# dv_spectrum_row.net
KiCad netlist of a schematic drawn in Altium Designer
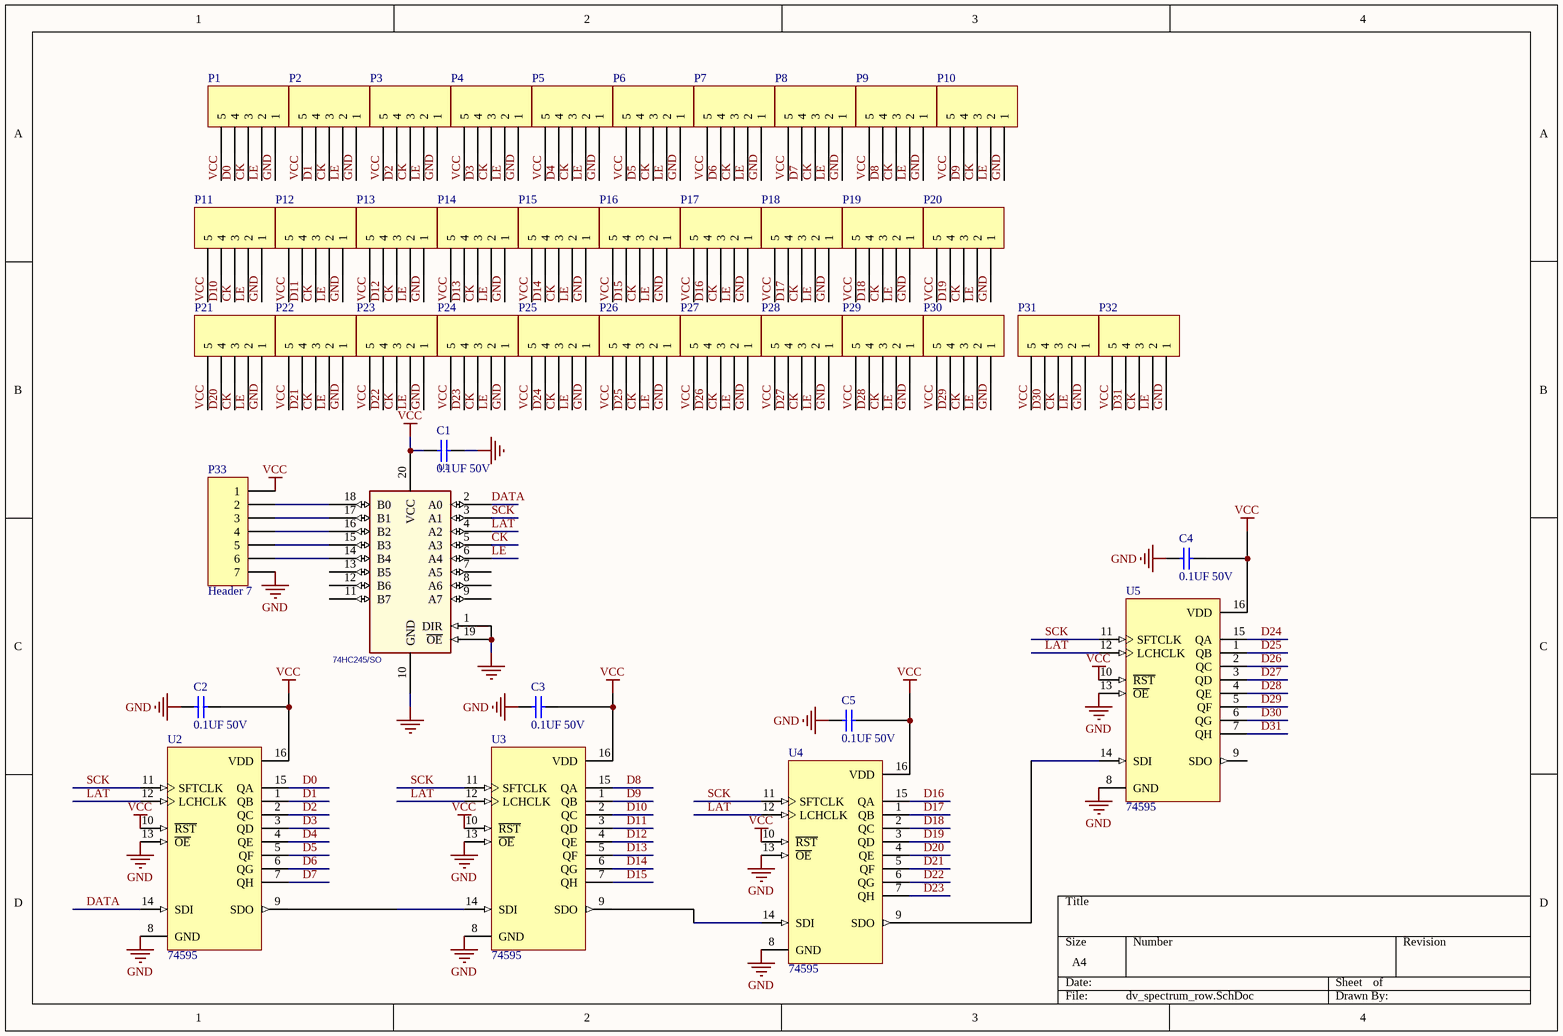
[diagram p0: dv_spectrum_row.SchDoc]

(export (version "E")
  (design (tool "Eeschema 10.0.6"))
  (components
    (comp (ref "C1")
      (value "0.1UF 50V")
      (footprint "CAPC2012X135N")
      (description "CAP CER 0.1UF 50V Y5V 0805")
      (fields
        (field (name "MANUFACTURER") "Yageo")
        (field (name "MANUFACTURER PART NUMBER") "CC0805ZRY5V9BB104")
      )
      (libsource (lib "altium-import") (part "root_1_CC0805ZRY5V9BB104_"))
    )
    (comp (ref "C2")
      (value "0.1UF 50V")
      (footprint "CAPC2012X135N")
      (description "CAP CER 0.1UF 50V Y5V 0805")
      (fields
        (field (name "MANUFACTURER") "Yageo")
        (field (name "MANUFACTURER PART NUMBER") "CC0805ZRY5V9BB104")
      )
      (libsource (lib "altium-import") (part "root_3_CC0805ZRY5V9BB104_"))
    )
    (comp (ref "C3")
      (value "0.1UF 50V")
      (footprint "CAPC2012X135N")
      (description "CAP CER 0.1UF 50V Y5V 0805")
      (fields
        (field (name "MANUFACTURER") "Yageo")
        (field (name "MANUFACTURER PART NUMBER") "CC0805ZRY5V9BB104")
      )
      (libsource (lib "altium-import") (part "root_1_CC0805ZRY5V9BB104_"))
    )
    (comp (ref "C4")
      (value "0.1UF 50V")
      (footprint "CAPC2012X135N")
      (description "CAP CER 0.1UF 50V Y5V 0805")
      (fields
        (field (name "MANUFACTURER") "Yageo")
        (field (name "MANUFACTURER PART NUMBER") "CC0805ZRY5V9BB104")
      )
      (libsource (lib "altium-import") (part "root_1_CC0805ZRY5V9BB104_"))
    )
    (comp (ref "C5")
      (value "0.1UF 50V")
      (footprint "CAPC2012X135N")
      (description "CAP CER 0.1UF 50V Y5V 0805")
      (fields
        (field (name "MANUFACTURER") "Yageo")
        (field (name "MANUFACTURER PART NUMBER") "CC0805ZRY5V9BB104")
      )
      (libsource (lib "altium-import") (part "root_1_CC0805ZRY5V9BB104_"))
    )
    (comp (ref "P1")
      (value "Header 5")
      (footprint "HDR1X5")
      (description "Header, 5-Pin")
      (fields (field (name "PUBLISHER") "Altium Limited"))
      (libsource (lib "Miscellaneous Connectors") (part "Header 5"))
    )
    (comp (ref "P2")
      (value "Header 5")
      (footprint "HDR1X5")
      (description "Header, 5-Pin")
      (fields (field (name "PUBLISHER") "Altium Limited"))
      (libsource (lib "Miscellaneous Connectors") (part "Header 5"))
    )
    (comp (ref "P3")
      (value "Header 5")
      (footprint "HDR1X5")
      (description "Header, 5-Pin")
      (fields (field (name "PUBLISHER") "Altium Limited"))
      (libsource (lib "Miscellaneous Connectors") (part "Header 5"))
    )
    (comp (ref "P4")
      (value "Header 5")
      (footprint "HDR1X5")
      (description "Header, 5-Pin")
      (fields (field (name "PUBLISHER") "Altium Limited"))
      (libsource (lib "Miscellaneous Connectors") (part "Header 5"))
    )
    (comp (ref "P5")
      (value "Header 5")
      (footprint "HDR1X5")
      (description "Header, 5-Pin")
      (fields (field (name "PUBLISHER") "Altium Limited"))
      (libsource (lib "Miscellaneous Connectors") (part "Header 5"))
    )
    (comp (ref "P6")
      (value "Header 5")
      (footprint "HDR1X5")
      (description "Header, 5-Pin")
      (fields (field (name "PUBLISHER") "Altium Limited"))
      (libsource (lib "Miscellaneous Connectors") (part "Header 5"))
    )
    (comp (ref "P7")
      (value "Header 5")
      (footprint "HDR1X5")
      (description "Header, 5-Pin")
      (fields (field (name "PUBLISHER") "Altium Limited"))
      (libsource (lib "Miscellaneous Connectors") (part "Header 5"))
    )
    (comp (ref "P8")
      (value "Header 5")
      (footprint "HDR1X5")
      (description "Header, 5-Pin")
      (fields (field (name "PUBLISHER") "Altium Limited"))
      (libsource (lib "Miscellaneous Connectors") (part "Header 5"))
    )
    (comp (ref "P9")
      (value "Header 5")
      (footprint "HDR1X5")
      (description "Header, 5-Pin")
      (fields (field (name "PUBLISHER") "Altium Limited"))
      (libsource (lib "Miscellaneous Connectors") (part "Header 5"))
    )
    (comp (ref "P10")
      (value "Header 5")
      (footprint "HDR1X5")
      (description "Header, 5-Pin")
      (fields (field (name "PUBLISHER") "Altium Limited"))
      (libsource (lib "Miscellaneous Connectors") (part "Header 5"))
    )
    (comp (ref "P11")
      (value "Header 5")
      (footprint "HDR1X5")
      (description "Header, 5-Pin")
      (fields (field (name "PUBLISHER") "Altium Limited"))
      (libsource (lib "Miscellaneous Connectors") (part "Header 5"))
    )
    (comp (ref "P12")
      (value "Header 5")
      (footprint "HDR1X5")
      (description "Header, 5-Pin")
      (fields (field (name "PUBLISHER") "Altium Limited"))
      (libsource (lib "Miscellaneous Connectors") (part "Header 5"))
    )
    (comp (ref "P13")
      (value "Header 5")
      (footprint "HDR1X5")
      (description "Header, 5-Pin")
      (fields (field (name "PUBLISHER") "Altium Limited"))
      (libsource (lib "Miscellaneous Connectors") (part "Header 5"))
    )
    (comp (ref "P14")
      (value "Header 5")
      (footprint "HDR1X5")
      (description "Header, 5-Pin")
      (fields (field (name "PUBLISHER") "Altium Limited"))
      (libsource (lib "Miscellaneous Connectors") (part "Header 5"))
    )
    (comp (ref "P15")
      (value "Header 5")
      (footprint "HDR1X5")
      (description "Header, 5-Pin")
      (fields (field (name "PUBLISHER") "Altium Limited"))
      (libsource (lib "Miscellaneous Connectors") (part "Header 5"))
    )
    (comp (ref "P16")
      (value "Header 5")
      (footprint "HDR1X5")
      (description "Header, 5-Pin")
      (fields (field (name "PUBLISHER") "Altium Limited"))
      (libsource (lib "Miscellaneous Connectors") (part "Header 5"))
    )
    (comp (ref "P17")
      (value "Header 5")
      (footprint "HDR1X5")
      (description "Header, 5-Pin")
      (fields (field (name "PUBLISHER") "Altium Limited"))
      (libsource (lib "Miscellaneous Connectors") (part "Header 5"))
    )
    (comp (ref "P18")
      (value "Header 5")
      (footprint "HDR1X5")
      (description "Header, 5-Pin")
      (fields (field (name "PUBLISHER") "Altium Limited"))
      (libsource (lib "Miscellaneous Connectors") (part "Header 5"))
    )
    (comp (ref "P19")
      (value "Header 5")
      (footprint "HDR1X5")
      (description "Header, 5-Pin")
      (fields (field (name "PUBLISHER") "Altium Limited"))
      (libsource (lib "Miscellaneous Connectors") (part "Header 5"))
    )
    (comp (ref "P20")
      (value "Header 5")
      (footprint "HDR1X5")
      (description "Header, 5-Pin")
      (fields (field (name "PUBLISHER") "Altium Limited"))
      (libsource (lib "Miscellaneous Connectors") (part "Header 5"))
    )
    (comp (ref "P21")
      (value "Header 5")
      (footprint "HDR1X5")
      (description "Header, 5-Pin")
      (fields (field (name "PUBLISHER") "Altium Limited"))
      (libsource (lib "Miscellaneous Connectors") (part "Header 5"))
    )
    (comp (ref "P22")
      (value "Header 5")
      (footprint "HDR1X5")
      (description "Header, 5-Pin")
      (fields (field (name "PUBLISHER") "Altium Limited"))
      (libsource (lib "Miscellaneous Connectors") (part "Header 5"))
    )
    (comp (ref "P23")
      (value "Header 5")
      (footprint "HDR1X5")
      (description "Header, 5-Pin")
      (fields (field (name "PUBLISHER") "Altium Limited"))
      (libsource (lib "Miscellaneous Connectors") (part "Header 5"))
    )
    (comp (ref "P24")
      (value "Header 5")
      (footprint "HDR1X5")
      (description "Header, 5-Pin")
      (fields (field (name "PUBLISHER") "Altium Limited"))
      (libsource (lib "Miscellaneous Connectors") (part "Header 5"))
    )
    (comp (ref "P25")
      (value "Header 5")
      (footprint "HDR1X5")
      (description "Header, 5-Pin")
      (fields (field (name "PUBLISHER") "Altium Limited"))
      (libsource (lib "Miscellaneous Connectors") (part "Header 5"))
    )
    (comp (ref "P26")
      (value "Header 5")
      (footprint "HDR1X5")
      (description "Header, 5-Pin")
      (fields (field (name "PUBLISHER") "Altium Limited"))
      (libsource (lib "Miscellaneous Connectors") (part "Header 5"))
    )
    (comp (ref "P27")
      (value "Header 5")
      (footprint "HDR1X5")
      (description "Header, 5-Pin")
      (fields (field (name "PUBLISHER") "Altium Limited"))
      (libsource (lib "Miscellaneous Connectors") (part "Header 5"))
    )
    (comp (ref "P28")
      (value "Header 5")
      (footprint "HDR1X5")
      (description "Header, 5-Pin")
      (fields (field (name "PUBLISHER") "Altium Limited"))
      (libsource (lib "Miscellaneous Connectors") (part "Header 5"))
    )
    (comp (ref "P29")
      (value "Header 5")
      (footprint "HDR1X5")
      (description "Header, 5-Pin")
      (fields (field (name "PUBLISHER") "Altium Limited"))
      (libsource (lib "Miscellaneous Connectors") (part "Header 5"))
    )
    (comp (ref "P30")
      (value "Header 5")
      (footprint "HDR1X5")
      (description "Header, 5-Pin")
      (fields (field (name "PUBLISHER") "Altium Limited"))
      (libsource (lib "Miscellaneous Connectors") (part "Header 5"))
    )
    (comp (ref "P31")
      (value "Header 5")
      (footprint "HDR1X5")
      (description "Header, 5-Pin")
      (fields (field (name "PUBLISHER") "Altium Limited"))
      (libsource (lib "Miscellaneous Connectors") (part "Header 5"))
    )
    (comp (ref "P32")
      (value "Header 5")
      (footprint "HDR1X5")
      (description "Header, 5-Pin")
      (fields (field (name "PUBLISHER") "Altium Limited"))
      (libsource (lib "Miscellaneous Connectors") (part "Header 5"))
    )
    (comp (ref "P33")
      (value "Header 7")
      (footprint "HDR1X7")
      (description "Header, 7-Pin")
      (fields (field (name "PUBLISHER") "Altium Limited"))
      (libsource (lib "Miscellaneous Connectors") (part "Header 7"))
    )
    (comp (ref "U1") (value "74HC245/SO") (libsource (lib "*") (part "74HC245/SO_1")))
    (comp (ref "U2")
      (value "74595")
      (footprint "SO16-150mil")
      (description "8-Bit Serial-Input/Serial or Prallel-Output Shift Register with Latched 3-State Outputs")
      (fields (field (name "PUBLISHER") "Altium Limited"))
      (libsource (lib "General IC") (part "74595"))
    )
    (comp (ref "U3")
      (value "74595")
      (footprint "SO16-150mil")
      (description "8-Bit Serial-Input/Serial or Prallel-Output Shift Register with Latched 3-State Outputs")
      (fields (field (name "PUBLISHER") "Altium Limited"))
      (libsource (lib "General IC") (part "74595"))
    )
    (comp (ref "U4")
      (value "74595")
      (footprint "SO16-150mil")
      (description "8-Bit Serial-Input/Serial or Prallel-Output Shift Register with Latched 3-State Outputs")
      (fields (field (name "PUBLISHER") "Altium Limited"))
      (libsource (lib "General IC") (part "74595"))
    )
    (comp (ref "U5")
      (value "74595")
      (footprint "SO16-150mil")
      (description "8-Bit Serial-Input/Serial or Prallel-Output Shift Register with Latched 3-State Outputs")
      (fields (field (name "PUBLISHER") "Altium Limited"))
      (libsource (lib "General IC") (part "74595"))
    )
  )
  (nets
    (net (code "1") (name "/CK") (class "Default")
      (node (ref "P1") (pin "3") (pinfunction "3_3") (pintype "passive"))
      (node (ref "P10") (pin "3") (pinfunction "3_3") (pintype "passive"))
      (node (ref "P11") (pin "3") (pinfunction "3_3") (pintype "passive"))
      (node (ref "P12") (pin "3") (pinfunction "3_3") (pintype "passive"))
      (node (ref "P13") (pin "3") (pinfunction "3_3") (pintype "passive"))
      (node (ref "P14") (pin "3") (pinfunction "3_3") (pintype "passive"))
      (node (ref "P15") (pin "3") (pinfunction "3_3") (pintype "passive"))
      (node (ref "P16") (pin "3") (pinfunction "3_3") (pintype "passive"))
      (node (ref "P17") (pin "3") (pinfunction "3_3") (pintype "passive"))
      (node (ref "P18") (pin "3") (pinfunction "3_3") (pintype "passive"))
      (node (ref "P19") (pin "3") (pinfunction "3_3") (pintype "passive"))
      (node (ref "P2") (pin "3") (pinfunction "3_3") (pintype "passive"))
      (node (ref "P20") (pin "3") (pinfunction "3_3") (pintype "passive"))
      (node (ref "P21") (pin "3") (pinfunction "3_3") (pintype "passive"))
      (node (ref "P22") (pin "3") (pinfunction "3_3") (pintype "passive"))
      (node (ref "P23") (pin "3") (pinfunction "3_3") (pintype "passive"))
      (node (ref "P24") (pin "3") (pinfunction "3_3") (pintype "passive"))
      (node (ref "P25") (pin "3") (pinfunction "3_3") (pintype "passive"))
      (node (ref "P26") (pin "3") (pinfunction "3_3") (pintype "passive"))
      (node (ref "P27") (pin "3") (pinfunction "3_3") (pintype "passive"))
      (node (ref "P28") (pin "3") (pinfunction "3_3") (pintype "passive"))
      (node (ref "P29") (pin "3") (pinfunction "3_3") (pintype "passive"))
      (node (ref "P3") (pin "3") (pinfunction "3_3") (pintype "passive"))
      (node (ref "P30") (pin "3") (pinfunction "3_3") (pintype "passive"))
      (node (ref "P31") (pin "3") (pinfunction "3_3") (pintype "passive"))
      (node (ref "P32") (pin "3") (pinfunction "3_3") (pintype "passive"))
      (node (ref "P4") (pin "3") (pinfunction "3_3") (pintype "passive"))
      (node (ref "P5") (pin "3") (pinfunction "3_3") (pintype "passive"))
      (node (ref "P6") (pin "3") (pinfunction "3_3") (pintype "passive"))
      (node (ref "P7") (pin "3") (pinfunction "3_3") (pintype "passive"))
      (node (ref "P8") (pin "3") (pinfunction "3_3") (pintype "passive"))
      (node (ref "P9") (pin "3") (pinfunction "3_3") (pintype "passive"))
      (node (ref "U1") (pin "5") (pinfunction "A3_5") (pintype "bidirectional"))
    )
    (net (code "2") (name "/D0") (class "Default")
      (node (ref "P1") (pin "4") (pinfunction "4_4") (pintype "passive"))
      (node (ref "U2") (pin "15") (pinfunction "QA_15") (pintype "tri_state"))
    )
    (net (code "3") (name "/D1") (class "Default")
      (node (ref "P2") (pin "4") (pinfunction "4_4") (pintype "passive"))
      (node (ref "U2") (pin "1") (pinfunction "QB_1") (pintype "tri_state"))
    )
    (net (code "4") (name "/D2") (class "Default")
      (node (ref "P3") (pin "4") (pinfunction "4_4") (pintype "passive"))
      (node (ref "U2") (pin "2") (pinfunction "QC_2") (pintype "tri_state"))
    )
    (net (code "5") (name "/D3") (class "Default")
      (node (ref "P4") (pin "4") (pinfunction "4_4") (pintype "passive"))
      (node (ref "U2") (pin "3") (pinfunction "QD_3") (pintype "tri_state"))
    )
    (net (code "6") (name "/D4") (class "Default")
      (node (ref "P5") (pin "4") (pinfunction "4_4") (pintype "passive"))
      (node (ref "U2") (pin "4") (pinfunction "QE_4") (pintype "tri_state"))
    )
    (net (code "7") (name "/D5") (class "Default")
      (node (ref "P6") (pin "4") (pinfunction "4_4") (pintype "passive"))
      (node (ref "U2") (pin "5") (pinfunction "QF_5") (pintype "tri_state"))
    )
    (net (code "8") (name "/D6") (class "Default")
      (node (ref "P7") (pin "4") (pinfunction "4_4") (pintype "passive"))
      (node (ref "U2") (pin "6") (pinfunction "QG_6") (pintype "tri_state"))
    )
    (net (code "9") (name "/D7") (class "Default")
      (node (ref "P8") (pin "4") (pinfunction "4_4") (pintype "passive"))
      (node (ref "U2") (pin "7") (pinfunction "QH_7") (pintype "tri_state"))
    )
    (net (code "10") (name "/D8") (class "Default")
      (node (ref "P9") (pin "4") (pinfunction "4_4") (pintype "passive"))
      (node (ref "U3") (pin "15") (pinfunction "QA_15") (pintype "tri_state"))
    )
    (net (code "11") (name "/D9") (class "Default")
      (node (ref "P10") (pin "4") (pinfunction "4_4") (pintype "passive"))
      (node (ref "U3") (pin "1") (pinfunction "QB_1") (pintype "tri_state"))
    )
    (net (code "12") (name "/D10") (class "Default")
      (node (ref "P11") (pin "4") (pinfunction "4_4") (pintype "passive"))
      (node (ref "U3") (pin "2") (pinfunction "QC_2") (pintype "tri_state"))
    )
    (net (code "13") (name "/D11") (class "Default")
      (node (ref "P12") (pin "4") (pinfunction "4_4") (pintype "passive"))
      (node (ref "U3") (pin "3") (pinfunction "QD_3") (pintype "tri_state"))
    )
    (net (code "14") (name "/D12") (class "Default")
      (node (ref "P13") (pin "4") (pinfunction "4_4") (pintype "passive"))
      (node (ref "U3") (pin "4") (pinfunction "QE_4") (pintype "tri_state"))
    )
    (net (code "15") (name "/D13") (class "Default")
      (node (ref "P14") (pin "4") (pinfunction "4_4") (pintype "passive"))
      (node (ref "U3") (pin "5") (pinfunction "QF_5") (pintype "tri_state"))
    )
    (net (code "16") (name "/D14") (class "Default")
      (node (ref "P15") (pin "4") (pinfunction "4_4") (pintype "passive"))
      (node (ref "U3") (pin "6") (pinfunction "QG_6") (pintype "tri_state"))
    )
    (net (code "17") (name "/D15") (class "Default")
      (node (ref "P16") (pin "4") (pinfunction "4_4") (pintype "passive"))
      (node (ref "U3") (pin "7") (pinfunction "QH_7") (pintype "tri_state"))
    )
    (net (code "18") (name "/D16") (class "Default")
      (node (ref "P17") (pin "4") (pinfunction "4_4") (pintype "passive"))
      (node (ref "U4") (pin "15") (pinfunction "QA_15") (pintype "tri_state"))
    )
    (net (code "19") (name "/D17") (class "Default")
      (node (ref "P18") (pin "4") (pinfunction "4_4") (pintype "passive"))
      (node (ref "U4") (pin "1") (pinfunction "QB_1") (pintype "tri_state"))
    )
    (net (code "20") (name "/D18") (class "Default")
      (node (ref "P19") (pin "4") (pinfunction "4_4") (pintype "passive"))
      (node (ref "U4") (pin "2") (pinfunction "QC_2") (pintype "tri_state"))
    )
    (net (code "21") (name "/D19") (class "Default")
      (node (ref "P20") (pin "4") (pinfunction "4_4") (pintype "passive"))
      (node (ref "U4") (pin "3") (pinfunction "QD_3") (pintype "tri_state"))
    )
    (net (code "22") (name "/D20") (class "Default")
      (node (ref "P21") (pin "4") (pinfunction "4_4") (pintype "passive"))
      (node (ref "U4") (pin "4") (pinfunction "QE_4") (pintype "tri_state"))
    )
    (net (code "23") (name "/D21") (class "Default")
      (node (ref "P22") (pin "4") (pinfunction "4_4") (pintype "passive"))
      (node (ref "U4") (pin "5") (pinfunction "QF_5") (pintype "tri_state"))
    )
    (net (code "24") (name "/D22") (class "Default")
      (node (ref "P23") (pin "4") (pinfunction "4_4") (pintype "passive"))
      (node (ref "U4") (pin "6") (pinfunction "QG_6") (pintype "tri_state"))
    )
    (net (code "25") (name "/D23") (class "Default")
      (node (ref "P24") (pin "4") (pinfunction "4_4") (pintype "passive"))
      (node (ref "U4") (pin "7") (pinfunction "QH_7") (pintype "tri_state"))
    )
    (net (code "26") (name "/D24") (class "Default")
      (node (ref "P25") (pin "4") (pinfunction "4_4") (pintype "passive"))
      (node (ref "U5") (pin "15") (pinfunction "QA_15") (pintype "tri_state"))
    )
    (net (code "27") (name "/D25") (class "Default")
      (node (ref "P26") (pin "4") (pinfunction "4_4") (pintype "passive"))
      (node (ref "U5") (pin "1") (pinfunction "QB_1") (pintype "tri_state"))
    )
    (net (code "28") (name "/D26") (class "Default")
      (node (ref "P27") (pin "4") (pinfunction "4_4") (pintype "passive"))
      (node (ref "U5") (pin "2") (pinfunction "QC_2") (pintype "tri_state"))
    )
    (net (code "29") (name "/D27") (class "Default")
      (node (ref "P28") (pin "4") (pinfunction "4_4") (pintype "passive"))
      (node (ref "U5") (pin "3") (pinfunction "QD_3") (pintype "tri_state"))
    )
    (net (code "30") (name "/D28") (class "Default")
      (node (ref "P29") (pin "4") (pinfunction "4_4") (pintype "passive"))
      (node (ref "U5") (pin "4") (pinfunction "QE_4") (pintype "tri_state"))
    )
    (net (code "31") (name "/D29") (class "Default")
      (node (ref "P30") (pin "4") (pinfunction "4_4") (pintype "passive"))
      (node (ref "U5") (pin "5") (pinfunction "QF_5") (pintype "tri_state"))
    )
    (net (code "32") (name "/D30") (class "Default")
      (node (ref "P31") (pin "4") (pinfunction "4_4") (pintype "passive"))
      (node (ref "U5") (pin "6") (pinfunction "QG_6") (pintype "tri_state"))
    )
    (net (code "33") (name "/D31") (class "Default")
      (node (ref "P32") (pin "4") (pinfunction "4_4") (pintype "passive"))
      (node (ref "U5") (pin "7") (pinfunction "QH_7") (pintype "tri_state"))
    )
    (net (code "34") (name "/DATA") (class "Default")
      (node (ref "U1") (pin "2") (pinfunction "A0_2") (pintype "bidirectional"))
      (node (ref "U2") (pin "14") (pinfunction "SDI_14") (pintype "input"))
    )
    (net (code "35") (name "/LAT") (class "Default")
      (node (ref "U1") (pin "4") (pinfunction "A2_4") (pintype "bidirectional"))
      (node (ref "U2") (pin "12") (pinfunction "LCHCLK_12") (pintype "input"))
      (node (ref "U3") (pin "12") (pinfunction "LCHCLK_12") (pintype "input"))
      (node (ref "U4") (pin "12") (pinfunction "LCHCLK_12") (pintype "input"))
      (node (ref "U5") (pin "12") (pinfunction "LCHCLK_12") (pintype "input"))
    )
    (net (code "36") (name "/LE") (class "Default")
      (node (ref "P1") (pin "2") (pinfunction "2_2") (pintype "passive"))
      (node (ref "P10") (pin "2") (pinfunction "2_2") (pintype "passive"))
      (node (ref "P11") (pin "2") (pinfunction "2_2") (pintype "passive"))
      (node (ref "P12") (pin "2") (pinfunction "2_2") (pintype "passive"))
      (node (ref "P13") (pin "2") (pinfunction "2_2") (pintype "passive"))
      (node (ref "P14") (pin "2") (pinfunction "2_2") (pintype "passive"))
      (node (ref "P15") (pin "2") (pinfunction "2_2") (pintype "passive"))
      (node (ref "P16") (pin "2") (pinfunction "2_2") (pintype "passive"))
      (node (ref "P17") (pin "2") (pinfunction "2_2") (pintype "passive"))
      (node (ref "P18") (pin "2") (pinfunction "2_2") (pintype "passive"))
      (node (ref "P19") (pin "2") (pinfunction "2_2") (pintype "passive"))
      (node (ref "P2") (pin "2") (pinfunction "2_2") (pintype "passive"))
      (node (ref "P20") (pin "2") (pinfunction "2_2") (pintype "passive"))
      (node (ref "P21") (pin "2") (pinfunction "2_2") (pintype "passive"))
      (node (ref "P22") (pin "2") (pinfunction "2_2") (pintype "passive"))
      (node (ref "P23") (pin "2") (pinfunction "2_2") (pintype "passive"))
      (node (ref "P24") (pin "2") (pinfunction "2_2") (pintype "passive"))
      (node (ref "P25") (pin "2") (pinfunction "2_2") (pintype "passive"))
      (node (ref "P26") (pin "2") (pinfunction "2_2") (pintype "passive"))
      (node (ref "P27") (pin "2") (pinfunction "2_2") (pintype "passive"))
      (node (ref "P28") (pin "2") (pinfunction "2_2") (pintype "passive"))
      (node (ref "P29") (pin "2") (pinfunction "2_2") (pintype "passive"))
      (node (ref "P3") (pin "2") (pinfunction "2_2") (pintype "passive"))
      (node (ref "P30") (pin "2") (pinfunction "2_2") (pintype "passive"))
      (node (ref "P31") (pin "2") (pinfunction "2_2") (pintype "passive"))
      (node (ref "P32") (pin "2") (pinfunction "2_2") (pintype "passive"))
      (node (ref "P4") (pin "2") (pinfunction "2_2") (pintype "passive"))
      (node (ref "P5") (pin "2") (pinfunction "2_2") (pintype "passive"))
      (node (ref "P6") (pin "2") (pinfunction "2_2") (pintype "passive"))
      (node (ref "P7") (pin "2") (pinfunction "2_2") (pintype "passive"))
      (node (ref "P8") (pin "2") (pinfunction "2_2") (pintype "passive"))
      (node (ref "P9") (pin "2") (pinfunction "2_2") (pintype "passive"))
      (node (ref "U1") (pin "6") (pinfunction "A4_6") (pintype "bidirectional"))
    )
    (net (code "37") (name "/SCK") (class "Default")
      (node (ref "U1") (pin "3") (pinfunction "A1_3") (pintype "bidirectional"))
      (node (ref "U2") (pin "11") (pinfunction "SFTCLK_11") (pintype "input"))
      (node (ref "U3") (pin "11") (pinfunction "SFTCLK_11") (pintype "input"))
      (node (ref "U4") (pin "11") (pinfunction "SFTCLK_11") (pintype "input"))
      (node (ref "U5") (pin "11") (pinfunction "SFTCLK_11") (pintype "input"))
    )
    (net (code "38") (name "GND") (class "Default")
      (node (ref "C1") (pin "1") (pinfunction "1_1") (pintype "passive"))
      (node (ref "C2") (pin "1") (pinfunction "1_1") (pintype "passive"))
      (node (ref "C3") (pin "2") (pinfunction "2_2") (pintype "passive"))
      (node (ref "C4") (pin "2") (pinfunction "2_2") (pintype "passive"))
      (node (ref "C5") (pin "2") (pinfunction "2_2") (pintype "passive"))
      (node (ref "P1") (pin "1") (pinfunction "1_1") (pintype "passive"))
      (node (ref "P10") (pin "1") (pinfunction "1_1") (pintype "passive"))
      (node (ref "P11") (pin "1") (pinfunction "1_1") (pintype "passive"))
      (node (ref "P12") (pin "1") (pinfunction "1_1") (pintype "passive"))
      (node (ref "P13") (pin "1") (pinfunction "1_1") (pintype "passive"))
      (node (ref "P14") (pin "1") (pinfunction "1_1") (pintype "passive"))
      (node (ref "P15") (pin "1") (pinfunction "1_1") (pintype "passive"))
      (node (ref "P16") (pin "1") (pinfunction "1_1") (pintype "passive"))
      (node (ref "P17") (pin "1") (pinfunction "1_1") (pintype "passive"))
      (node (ref "P18") (pin "1") (pinfunction "1_1") (pintype "passive"))
      (node (ref "P19") (pin "1") (pinfunction "1_1") (pintype "passive"))
      (node (ref "P2") (pin "1") (pinfunction "1_1") (pintype "passive"))
      (node (ref "P20") (pin "1") (pinfunction "1_1") (pintype "passive"))
      (node (ref "P21") (pin "1") (pinfunction "1_1") (pintype "passive"))
      (node (ref "P22") (pin "1") (pinfunction "1_1") (pintype "passive"))
      (node (ref "P23") (pin "1") (pinfunction "1_1") (pintype "passive"))
      (node (ref "P24") (pin "1") (pinfunction "1_1") (pintype "passive"))
      (node (ref "P25") (pin "1") (pinfunction "1_1") (pintype "passive"))
      (node (ref "P26") (pin "1") (pinfunction "1_1") (pintype "passive"))
      (node (ref "P27") (pin "1") (pinfunction "1_1") (pintype "passive"))
      (node (ref "P28") (pin "1") (pinfunction "1_1") (pintype "passive"))
      (node (ref "P29") (pin "1") (pinfunction "1_1") (pintype "passive"))
      (node (ref "P3") (pin "1") (pinfunction "1_1") (pintype "passive"))
      (node (ref "P30") (pin "1") (pinfunction "1_1") (pintype "passive"))
      (node (ref "P31") (pin "1") (pinfunction "1_1") (pintype "passive"))
      (node (ref "P32") (pin "1") (pinfunction "1_1") (pintype "passive"))
      (node (ref "P33") (pin "7") (pinfunction "7_7") (pintype "passive"))
      (node (ref "P4") (pin "1") (pinfunction "1_1") (pintype "passive"))
      (node (ref "P5") (pin "1") (pinfunction "1_1") (pintype "passive"))
      (node (ref "P6") (pin "1") (pinfunction "1_1") (pintype "passive"))
      (node (ref "P7") (pin "1") (pinfunction "1_1") (pintype "passive"))
      (node (ref "P8") (pin "1") (pinfunction "1_1") (pintype "passive"))
      (node (ref "P9") (pin "1") (pinfunction "1_1") (pintype "passive"))
      (node (ref "U1") (pin "1") (pinfunction "DIR_1") (pintype "input"))
      (node (ref "U1") (pin "10") (pinfunction "GND_10") (pintype "power_in"))
      (node (ref "U1") (pin "19") (pinfunction "~{OE}_19") (pintype "input"))
      (node (ref "U2") (pin "13") (pinfunction "~{OE}_13") (pintype "input"))
      (node (ref "U2") (pin "8") (pinfunction "GND_8") (pintype "power_in"))
      (node (ref "U3") (pin "13") (pinfunction "~{OE}_13") (pintype "input"))
      (node (ref "U3") (pin "8") (pinfunction "GND_8") (pintype "power_in"))
      (node (ref "U4") (pin "13") (pinfunction "~{OE}_13") (pintype "input"))
      (node (ref "U4") (pin "8") (pinfunction "GND_8") (pintype "power_in"))
      (node (ref "U5") (pin "13") (pinfunction "~{OE}_13") (pintype "input"))
      (node (ref "U5") (pin "8") (pinfunction "GND_8") (pintype "power_in"))
    )
    (net (code "39") (name "Net-(U1-B0)") (class "Default")
      (node (ref "P33") (pin "2") (pinfunction "2_2") (pintype "passive"))
      (node (ref "U1") (pin "18") (pinfunction "B0_18") (pintype "bidirectional"))
    )
    (net (code "40") (name "Net-(U1-B1)") (class "Default")
      (node (ref "P33") (pin "3") (pinfunction "3_3") (pintype "passive"))
      (node (ref "U1") (pin "17") (pinfunction "B1_17") (pintype "bidirectional"))
    )
    (net (code "41") (name "Net-(U1-B2)") (class "Default")
      (node (ref "P33") (pin "4") (pinfunction "4_4") (pintype "passive"))
      (node (ref "U1") (pin "16") (pinfunction "B2_16") (pintype "bidirectional"))
    )
    (net (code "42") (name "Net-(U1-B3)") (class "Default")
      (node (ref "P33") (pin "5") (pinfunction "5_5") (pintype "passive"))
      (node (ref "U1") (pin "15") (pinfunction "B3_15") (pintype "bidirectional"))
    )
    (net (code "43") (name "Net-(U1-B4)") (class "Default")
      (node (ref "P33") (pin "6") (pinfunction "6_6") (pintype "passive"))
      (node (ref "U1") (pin "14") (pinfunction "B4_14") (pintype "bidirectional"))
    )
    (net (code "44") (name "Net-(U2-SDO)") (class "Default")
      (node (ref "U2") (pin "9") (pinfunction "SDO_9") (pintype "output"))
      (node (ref "U3") (pin "14") (pinfunction "SDI_14") (pintype "input"))
    )
    (net (code "45") (name "Net-(U3-SDO)") (class "Default")
      (node (ref "U3") (pin "9") (pinfunction "SDO_9") (pintype "output"))
      (node (ref "U4") (pin "14") (pinfunction "SDI_14") (pintype "input"))
    )
    (net (code "46") (name "Net-(U4-SDO)") (class "Default")
      (node (ref "U4") (pin "9") (pinfunction "SDO_9") (pintype "output"))
      (node (ref "U5") (pin "14") (pinfunction "SDI_14") (pintype "input"))
    )
    (net (code "47") (name "VCC") (class "Default")
      (node (ref "C1") (pin "2") (pinfunction "2_2") (pintype "passive"))
      (node (ref "C2") (pin "2") (pinfunction "2_2") (pintype "passive"))
      (node (ref "C3") (pin "1") (pinfunction "1_1") (pintype "passive"))
      (node (ref "C4") (pin "1") (pinfunction "1_1") (pintype "passive"))
      (node (ref "C5") (pin "1") (pinfunction "1_1") (pintype "passive"))
      (node (ref "P1") (pin "5") (pinfunction "5_5") (pintype "passive"))
      (node (ref "P10") (pin "5") (pinfunction "5_5") (pintype "passive"))
      (node (ref "P11") (pin "5") (pinfunction "5_5") (pintype "passive"))
      (node (ref "P12") (pin "5") (pinfunction "5_5") (pintype "passive"))
      (node (ref "P13") (pin "5") (pinfunction "5_5") (pintype "passive"))
      (node (ref "P14") (pin "5") (pinfunction "5_5") (pintype "passive"))
      (node (ref "P15") (pin "5") (pinfunction "5_5") (pintype "passive"))
      (node (ref "P16") (pin "5") (pinfunction "5_5") (pintype "passive"))
      (node (ref "P17") (pin "5") (pinfunction "5_5") (pintype "passive"))
      (node (ref "P18") (pin "5") (pinfunction "5_5") (pintype "passive"))
      (node (ref "P19") (pin "5") (pinfunction "5_5") (pintype "passive"))
      (node (ref "P2") (pin "5") (pinfunction "5_5") (pintype "passive"))
      (node (ref "P20") (pin "5") (pinfunction "5_5") (pintype "passive"))
      (node (ref "P21") (pin "5") (pinfunction "5_5") (pintype "passive"))
      (node (ref "P22") (pin "5") (pinfunction "5_5") (pintype "passive"))
      (node (ref "P23") (pin "5") (pinfunction "5_5") (pintype "passive"))
      (node (ref "P24") (pin "5") (pinfunction "5_5") (pintype "passive"))
      (node (ref "P25") (pin "5") (pinfunction "5_5") (pintype "passive"))
      (node (ref "P26") (pin "5") (pinfunction "5_5") (pintype "passive"))
      (node (ref "P27") (pin "5") (pinfunction "5_5") (pintype "passive"))
      (node (ref "P28") (pin "5") (pinfunction "5_5") (pintype "passive"))
      (node (ref "P29") (pin "5") (pinfunction "5_5") (pintype "passive"))
      (node (ref "P3") (pin "5") (pinfunction "5_5") (pintype "passive"))
      (node (ref "P30") (pin "5") (pinfunction "5_5") (pintype "passive"))
      (node (ref "P31") (pin "5") (pinfunction "5_5") (pintype "passive"))
      (node (ref "P32") (pin "5") (pinfunction "5_5") (pintype "passive"))
      (node (ref "P33") (pin "1") (pinfunction "1_1") (pintype "passive"))
      (node (ref "P4") (pin "5") (pinfunction "5_5") (pintype "passive"))
      (node (ref "P5") (pin "5") (pinfunction "5_5") (pintype "passive"))
      (node (ref "P6") (pin "5") (pinfunction "5_5") (pintype "passive"))
      (node (ref "P7") (pin "5") (pinfunction "5_5") (pintype "passive"))
      (node (ref "P8") (pin "5") (pinfunction "5_5") (pintype "passive"))
      (node (ref "P9") (pin "5") (pinfunction "5_5") (pintype "passive"))
      (node (ref "U1") (pin "20") (pinfunction "VCC_20") (pintype "power_in"))
      (node (ref "U2") (pin "10") (pinfunction "~{RST}_10") (pintype "input"))
      (node (ref "U2") (pin "16") (pinfunction "VDD_16") (pintype "power_in"))
      (node (ref "U3") (pin "10") (pinfunction "~{RST}_10") (pintype "input"))
      (node (ref "U3") (pin "16") (pinfunction "VDD_16") (pintype "power_in"))
      (node (ref "U4") (pin "10") (pinfunction "~{RST}_10") (pintype "input"))
      (node (ref "U4") (pin "16") (pinfunction "VDD_16") (pintype "power_in"))
      (node (ref "U5") (pin "10") (pinfunction "~{RST}_10") (pintype "input"))
      (node (ref "U5") (pin "16") (pinfunction "VDD_16") (pintype "power_in"))
    )
    (net (code "48") (name "unconnected-(U1-A5-Pad7)") (class "Default")
      (node (ref "U1") (pin "7") (pinfunction "A5_7") (pintype "bidirectional"))
    )
    (net (code "49") (name "unconnected-(U1-A6-Pad8)") (class "Default")
      (node (ref "U1") (pin "8") (pinfunction "A6_8") (pintype "bidirectional"))
    )
    (net (code "50") (name "unconnected-(U1-A7-Pad9)") (class "Default")
      (node (ref "U1") (pin "9") (pinfunction "A7_9") (pintype "bidirectional"))
    )
    (net (code "51") (name "unconnected-(U1-B5-Pad13)") (class "Default")
      (node (ref "U1") (pin "13") (pinfunction "B5_13") (pintype "bidirectional"))
    )
    (net (code "52") (name "unconnected-(U1-B6-Pad12)") (class "Default")
      (node (ref "U1") (pin "12") (pinfunction "B6_12") (pintype "bidirectional"))
    )
    (net (code "53") (name "unconnected-(U1-B7-Pad11)") (class "Default")
      (node (ref "U1") (pin "11") (pinfunction "B7_11") (pintype "bidirectional"))
    )
    (net (code "54") (name "unconnected-(U5-SDO-Pad9)") (class "Default")
      (node (ref "U5") (pin "9") (pinfunction "SDO_9") (pintype "output"))
    )
  )
)
